# Microsecond_clock_LEDs.net
KiCad netlist of a schematic drawn in EAGLE
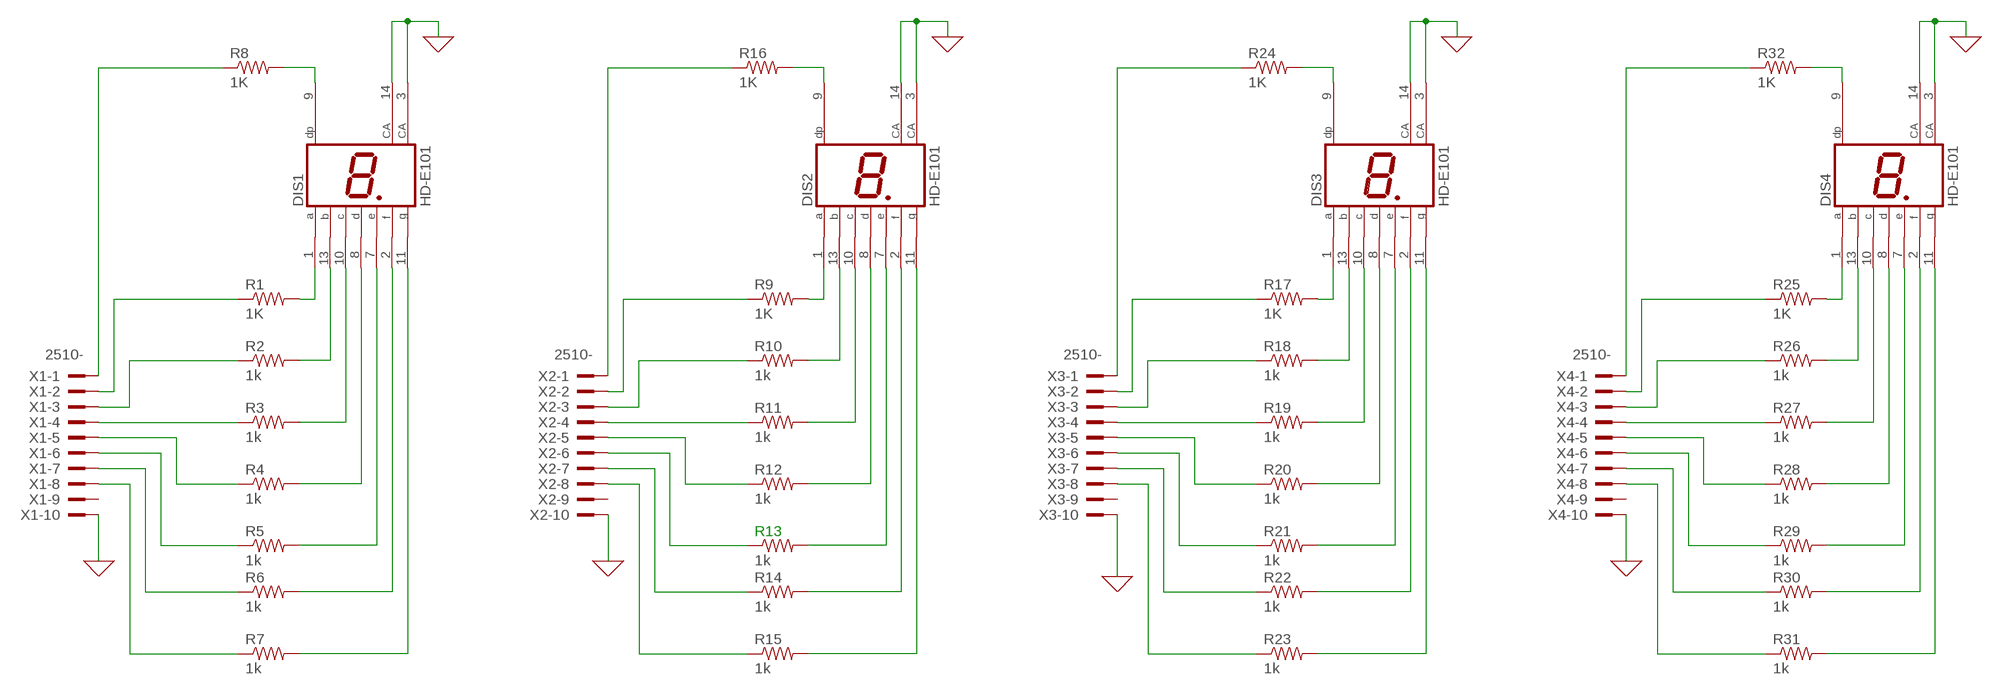
[diagram p0: schematic, sheet 1]

(export (version "E")
  (design (tool "Eeschema 10.0.6"))
  (components
    (comp (ref "DIS1")
      (value "HD-E101")
      (footprint "eagle-import:HDSP-I")
      (libsource (lib "eagle-import") (part "HD-E101"))
    )
    (comp (ref "DIS2")
      (value "HD-E101")
      (footprint "eagle-import:HDSP-I")
      (libsource (lib "eagle-import") (part "HD-E101"))
    )
    (comp (ref "DIS3")
      (value "HD-E101")
      (footprint "eagle-import:HDSP-I")
      (libsource (lib "eagle-import") (part "HD-E101"))
    )
    (comp (ref "DIS4")
      (value "HD-E101")
      (footprint "eagle-import:HDSP-I")
      (libsource (lib "eagle-import") (part "HD-E101"))
    )
    (comp (ref "R1")
      (value "1K")
      (footprint "eagle-import:0207_7")
      (libsource (lib "eagle-import") (part "R-US_0207/7"))
    )
    (comp (ref "R2")
      (value "1k")
      (footprint "eagle-import:0207_7")
      (libsource (lib "eagle-import") (part "R-US_0207/7"))
    )
    (comp (ref "R3")
      (value "1k")
      (footprint "eagle-import:0207_7")
      (libsource (lib "eagle-import") (part "R-US_0207/7"))
    )
    (comp (ref "R4")
      (value "1k")
      (footprint "eagle-import:0207_7")
      (libsource (lib "eagle-import") (part "R-US_0207/7"))
    )
    (comp (ref "R5")
      (value "1k")
      (footprint "eagle-import:0207_7")
      (libsource (lib "eagle-import") (part "R-US_0207/7"))
    )
    (comp (ref "R6")
      (value "1k")
      (footprint "eagle-import:0207_7")
      (libsource (lib "eagle-import") (part "R-US_0207/7"))
    )
    (comp (ref "R7")
      (value "1k")
      (footprint "eagle-import:0207_7")
      (libsource (lib "eagle-import") (part "R-US_0207/7"))
    )
    (comp (ref "R8")
      (value "1K")
      (footprint "eagle-import:0207_7")
      (libsource (lib "eagle-import") (part "R-US_0207/7"))
    )
    (comp (ref "R9")
      (value "1K")
      (footprint "eagle-import:0207_7")
      (libsource (lib "eagle-import") (part "R-US_0207/7"))
    )
    (comp (ref "R10")
      (value "1k")
      (footprint "eagle-import:0207_7")
      (libsource (lib "eagle-import") (part "R-US_0207/7"))
    )
    (comp (ref "R11")
      (value "1k")
      (footprint "eagle-import:0207_7")
      (libsource (lib "eagle-import") (part "R-US_0207/7"))
    )
    (comp (ref "R12")
      (value "1k")
      (footprint "eagle-import:0207_7")
      (libsource (lib "eagle-import") (part "R-US_0207/7"))
    )
    (comp (ref "R13")
      (value "1k")
      (footprint "eagle-import:0207_7")
      (libsource (lib "eagle-import") (part "R-US_0207/7"))
    )
    (comp (ref "R14")
      (value "1k")
      (footprint "eagle-import:0207_7")
      (libsource (lib "eagle-import") (part "R-US_0207/7"))
    )
    (comp (ref "R15")
      (value "1k")
      (footprint "eagle-import:0207_7")
      (libsource (lib "eagle-import") (part "R-US_0207/7"))
    )
    (comp (ref "R16")
      (value "1K")
      (footprint "eagle-import:0207_7")
      (libsource (lib "eagle-import") (part "R-US_0207/7"))
    )
    (comp (ref "R17")
      (value "1K")
      (footprint "eagle-import:0207_7")
      (libsource (lib "eagle-import") (part "R-US_0207/7"))
    )
    (comp (ref "R18")
      (value "1k")
      (footprint "eagle-import:0207_7")
      (libsource (lib "eagle-import") (part "R-US_0207/7"))
    )
    (comp (ref "R19")
      (value "1k")
      (footprint "eagle-import:0207_7")
      (libsource (lib "eagle-import") (part "R-US_0207/7"))
    )
    (comp (ref "R20")
      (value "1k")
      (footprint "eagle-import:0207_7")
      (libsource (lib "eagle-import") (part "R-US_0207/7"))
    )
    (comp (ref "R21")
      (value "1k")
      (footprint "eagle-import:0207_7")
      (libsource (lib "eagle-import") (part "R-US_0207/7"))
    )
    (comp (ref "R22")
      (value "1k")
      (footprint "eagle-import:0207_7")
      (libsource (lib "eagle-import") (part "R-US_0207/7"))
    )
    (comp (ref "R23")
      (value "1k")
      (footprint "eagle-import:0207_7")
      (libsource (lib "eagle-import") (part "R-US_0207/7"))
    )
    (comp (ref "R24")
      (value "1K")
      (footprint "eagle-import:0207_7")
      (libsource (lib "eagle-import") (part "R-US_0207/7"))
    )
    (comp (ref "R25")
      (value "1K")
      (footprint "eagle-import:0207_7")
      (libsource (lib "eagle-import") (part "R-US_0207/7"))
    )
    (comp (ref "R26")
      (value "1k")
      (footprint "eagle-import:0207_7")
      (libsource (lib "eagle-import") (part "R-US_0207/7"))
    )
    (comp (ref "R27")
      (value "1k")
      (footprint "eagle-import:0207_7")
      (libsource (lib "eagle-import") (part "R-US_0207/7"))
    )
    (comp (ref "R28")
      (value "1k")
      (footprint "eagle-import:0207_7")
      (libsource (lib "eagle-import") (part "R-US_0207/7"))
    )
    (comp (ref "R29")
      (value "1k")
      (footprint "eagle-import:0207_7")
      (libsource (lib "eagle-import") (part "R-US_0207/7"))
    )
    (comp (ref "R30")
      (value "1k")
      (footprint "eagle-import:0207_7")
      (libsource (lib "eagle-import") (part "R-US_0207/7"))
    )
    (comp (ref "R31")
      (value "1k")
      (footprint "eagle-import:0207_7")
      (libsource (lib "eagle-import") (part "R-US_0207/7"))
    )
    (comp (ref "R32")
      (value "1K")
      (footprint "eagle-import:0207_7")
      (libsource (lib "eagle-import") (part "R-US_0207/7"))
    )
    (comp (ref "X1")
      (value "2510-")
      (footprint "eagle-import:PAK100_2500-10")
      (fields (field (name "MF") "3M") (field (name "MPN") "2510-6002UB"))
      (libsource (lib "eagle-import") (part "2510-"))
    )
    (comp (ref "X2")
      (value "2510-")
      (footprint "eagle-import:PAK100_2500-10")
      (fields (field (name "MF") "3M") (field (name "MPN") "2510-6002UB"))
      (libsource (lib "eagle-import") (part "2510-"))
    )
    (comp (ref "X3")
      (value "2510-")
      (footprint "eagle-import:PAK100_2500-10")
      (fields (field (name "MF") "3M") (field (name "MPN") "2510-6002UB"))
      (libsource (lib "eagle-import") (part "2510-"))
    )
    (comp (ref "X4")
      (value "2510-")
      (footprint "eagle-import:PAK100_2500-10")
      (fields (field (name "MF") "3M") (field (name "MPN") "2510-6002UB"))
      (libsource (lib "eagle-import") (part "2510-"))
    )
  )
  (nets
    (net (code "1") (name "GND") (class "Default")
      (node (ref "DIS1") (pin "14") (pinfunction "CA_14") (pintype "passive"))
      (node (ref "DIS1") (pin "3") (pinfunction "CA_3") (pintype "passive"))
      (node (ref "DIS2") (pin "14") (pinfunction "CA_14") (pintype "passive"))
      (node (ref "DIS2") (pin "3") (pinfunction "CA_3") (pintype "passive"))
      (node (ref "DIS3") (pin "14") (pinfunction "CA_14") (pintype "passive"))
      (node (ref "DIS3") (pin "3") (pinfunction "CA_3") (pintype "passive"))
      (node (ref "DIS4") (pin "14") (pinfunction "CA_14") (pintype "passive"))
      (node (ref "DIS4") (pin "3") (pinfunction "CA_3") (pintype "passive"))
      (node (ref "X1") (pin "10") (pinfunction "KL_10") (pintype "passive"))
      (node (ref "X2") (pin "10") (pinfunction "KL_10") (pintype "passive"))
      (node (ref "X3") (pin "10") (pinfunction "KL_10") (pintype "passive"))
      (node (ref "X4") (pin "10") (pinfunction "KL_10") (pintype "passive"))
    )
    (net (code "2") (name "Net-(DIS1-A)") (class "Default")
      (node (ref "DIS1") (pin "1") (pinfunction "A_1") (pintype "passive"))
      (node (ref "R1") (pin "2") (pinfunction "2_2") (pintype "passive"))
    )
    (net (code "3") (name "Net-(DIS1-B)") (class "Default")
      (node (ref "DIS1") (pin "13") (pinfunction "B_13") (pintype "passive"))
      (node (ref "R2") (pin "2") (pinfunction "2_2") (pintype "passive"))
    )
    (net (code "4") (name "Net-(DIS1-C)") (class "Default")
      (node (ref "DIS1") (pin "10") (pinfunction "C_10") (pintype "passive"))
      (node (ref "R3") (pin "2") (pinfunction "2_2") (pintype "passive"))
    )
    (net (code "5") (name "Net-(DIS1-D)") (class "Default")
      (node (ref "DIS1") (pin "8") (pinfunction "D_8") (pintype "passive"))
      (node (ref "R4") (pin "2") (pinfunction "2_2") (pintype "passive"))
    )
    (net (code "6") (name "Net-(DIS1-DP)") (class "Default")
      (node (ref "DIS1") (pin "9") (pinfunction "DP_9") (pintype "passive"))
      (node (ref "R8") (pin "2") (pinfunction "2_2") (pintype "passive"))
    )
    (net (code "7") (name "Net-(DIS1-E)") (class "Default")
      (node (ref "DIS1") (pin "7") (pinfunction "E_7") (pintype "passive"))
      (node (ref "R5") (pin "2") (pinfunction "2_2") (pintype "passive"))
    )
    (net (code "8") (name "Net-(DIS1-F)") (class "Default")
      (node (ref "DIS1") (pin "2") (pinfunction "F_2") (pintype "passive"))
      (node (ref "R6") (pin "2") (pinfunction "2_2") (pintype "passive"))
    )
    (net (code "9") (name "Net-(DIS1-G)") (class "Default")
      (node (ref "DIS1") (pin "11") (pinfunction "G_11") (pintype "passive"))
      (node (ref "R7") (pin "2") (pinfunction "2_2") (pintype "passive"))
    )
    (net (code "10") (name "Net-(DIS2-A)") (class "Default")
      (node (ref "DIS2") (pin "1") (pinfunction "A_1") (pintype "passive"))
      (node (ref "R9") (pin "2") (pinfunction "2_2") (pintype "passive"))
    )
    (net (code "11") (name "Net-(DIS2-B)") (class "Default")
      (node (ref "DIS2") (pin "13") (pinfunction "B_13") (pintype "passive"))
      (node (ref "R10") (pin "2") (pinfunction "2_2") (pintype "passive"))
    )
    (net (code "12") (name "Net-(DIS2-C)") (class "Default")
      (node (ref "DIS2") (pin "10") (pinfunction "C_10") (pintype "passive"))
      (node (ref "R11") (pin "2") (pinfunction "2_2") (pintype "passive"))
    )
    (net (code "13") (name "Net-(DIS2-D)") (class "Default")
      (node (ref "DIS2") (pin "8") (pinfunction "D_8") (pintype "passive"))
      (node (ref "R12") (pin "2") (pinfunction "2_2") (pintype "passive"))
    )
    (net (code "14") (name "Net-(DIS2-DP)") (class "Default")
      (node (ref "DIS2") (pin "9") (pinfunction "DP_9") (pintype "passive"))
      (node (ref "R16") (pin "2") (pinfunction "2_2") (pintype "passive"))
    )
    (net (code "15") (name "Net-(DIS2-E)") (class "Default")
      (node (ref "DIS2") (pin "7") (pinfunction "E_7") (pintype "passive"))
      (node (ref "R13") (pin "2") (pinfunction "2_2") (pintype "passive"))
    )
    (net (code "16") (name "Net-(DIS2-F)") (class "Default")
      (node (ref "DIS2") (pin "2") (pinfunction "F_2") (pintype "passive"))
      (node (ref "R14") (pin "2") (pinfunction "2_2") (pintype "passive"))
    )
    (net (code "17") (name "Net-(DIS2-G)") (class "Default")
      (node (ref "DIS2") (pin "11") (pinfunction "G_11") (pintype "passive"))
      (node (ref "R15") (pin "2") (pinfunction "2_2") (pintype "passive"))
    )
    (net (code "18") (name "Net-(DIS3-A)") (class "Default")
      (node (ref "DIS3") (pin "1") (pinfunction "A_1") (pintype "passive"))
      (node (ref "R17") (pin "2") (pinfunction "2_2") (pintype "passive"))
    )
    (net (code "19") (name "Net-(DIS3-B)") (class "Default")
      (node (ref "DIS3") (pin "13") (pinfunction "B_13") (pintype "passive"))
      (node (ref "R18") (pin "2") (pinfunction "2_2") (pintype "passive"))
    )
    (net (code "20") (name "Net-(DIS3-C)") (class "Default")
      (node (ref "DIS3") (pin "10") (pinfunction "C_10") (pintype "passive"))
      (node (ref "R19") (pin "2") (pinfunction "2_2") (pintype "passive"))
    )
    (net (code "21") (name "Net-(DIS3-D)") (class "Default")
      (node (ref "DIS3") (pin "8") (pinfunction "D_8") (pintype "passive"))
      (node (ref "R20") (pin "2") (pinfunction "2_2") (pintype "passive"))
    )
    (net (code "22") (name "Net-(DIS3-DP)") (class "Default")
      (node (ref "DIS3") (pin "9") (pinfunction "DP_9") (pintype "passive"))
      (node (ref "R24") (pin "2") (pinfunction "2_2") (pintype "passive"))
    )
    (net (code "23") (name "Net-(DIS3-E)") (class "Default")
      (node (ref "DIS3") (pin "7") (pinfunction "E_7") (pintype "passive"))
      (node (ref "R21") (pin "2") (pinfunction "2_2") (pintype "passive"))
    )
    (net (code "24") (name "Net-(DIS3-F)") (class "Default")
      (node (ref "DIS3") (pin "2") (pinfunction "F_2") (pintype "passive"))
      (node (ref "R22") (pin "2") (pinfunction "2_2") (pintype "passive"))
    )
    (net (code "25") (name "Net-(DIS3-G)") (class "Default")
      (node (ref "DIS3") (pin "11") (pinfunction "G_11") (pintype "passive"))
      (node (ref "R23") (pin "2") (pinfunction "2_2") (pintype "passive"))
    )
    (net (code "26") (name "Net-(DIS4-A)") (class "Default")
      (node (ref "DIS4") (pin "1") (pinfunction "A_1") (pintype "passive"))
      (node (ref "R25") (pin "2") (pinfunction "2_2") (pintype "passive"))
    )
    (net (code "27") (name "Net-(DIS4-B)") (class "Default")
      (node (ref "DIS4") (pin "13") (pinfunction "B_13") (pintype "passive"))
      (node (ref "R26") (pin "2") (pinfunction "2_2") (pintype "passive"))
    )
    (net (code "28") (name "Net-(DIS4-C)") (class "Default")
      (node (ref "DIS4") (pin "10") (pinfunction "C_10") (pintype "passive"))
      (node (ref "R27") (pin "2") (pinfunction "2_2") (pintype "passive"))
    )
    (net (code "29") (name "Net-(DIS4-D)") (class "Default")
      (node (ref "DIS4") (pin "8") (pinfunction "D_8") (pintype "passive"))
      (node (ref "R28") (pin "2") (pinfunction "2_2") (pintype "passive"))
    )
    (net (code "30") (name "Net-(DIS4-DP)") (class "Default")
      (node (ref "DIS4") (pin "9") (pinfunction "DP_9") (pintype "passive"))
      (node (ref "R32") (pin "2") (pinfunction "2_2") (pintype "passive"))
    )
    (net (code "31") (name "Net-(DIS4-E)") (class "Default")
      (node (ref "DIS4") (pin "7") (pinfunction "E_7") (pintype "passive"))
      (node (ref "R29") (pin "2") (pinfunction "2_2") (pintype "passive"))
    )
    (net (code "32") (name "Net-(DIS4-F)") (class "Default")
      (node (ref "DIS4") (pin "2") (pinfunction "F_2") (pintype "passive"))
      (node (ref "R30") (pin "2") (pinfunction "2_2") (pintype "passive"))
    )
    (net (code "33") (name "Net-(DIS4-G)") (class "Default")
      (node (ref "DIS4") (pin "11") (pinfunction "G_11") (pintype "passive"))
      (node (ref "R31") (pin "2") (pinfunction "2_2") (pintype "passive"))
    )
    (net (code "34") (name "Net-(X1A-KL)") (class "Default")
      (node (ref "R8") (pin "1") (pinfunction "1_1") (pintype "passive"))
      (node (ref "X1") (pin "1") (pinfunction "KL_1") (pintype "passive"))
    )
    (net (code "35") (name "Net-(X1C-KL)") (class "Default")
      (node (ref "R1") (pin "1") (pinfunction "1_1") (pintype "passive"))
      (node (ref "X1") (pin "2") (pinfunction "KL_2") (pintype "passive"))
    )
    (net (code "36") (name "Net-(X1D-KL)") (class "Default")
      (node (ref "R2") (pin "1") (pinfunction "1_1") (pintype "passive"))
      (node (ref "X1") (pin "3") (pinfunction "KL_3") (pintype "passive"))
    )
    (net (code "37") (name "Net-(X1E-KL)") (class "Default")
      (node (ref "R3") (pin "1") (pinfunction "1_1") (pintype "passive"))
      (node (ref "X1") (pin "4") (pinfunction "KL_4") (pintype "passive"))
    )
    (net (code "38") (name "Net-(X1F-KL)") (class "Default")
      (node (ref "R4") (pin "1") (pinfunction "1_1") (pintype "passive"))
      (node (ref "X1") (pin "5") (pinfunction "KL_5") (pintype "passive"))
    )
    (net (code "39") (name "Net-(X1G-KL)") (class "Default")
      (node (ref "R5") (pin "1") (pinfunction "1_1") (pintype "passive"))
      (node (ref "X1") (pin "6") (pinfunction "KL_6") (pintype "passive"))
    )
    (net (code "40") (name "Net-(X1H-KL)") (class "Default")
      (node (ref "R6") (pin "1") (pinfunction "1_1") (pintype "passive"))
      (node (ref "X1") (pin "7") (pinfunction "KL_7") (pintype "passive"))
    )
    (net (code "41") (name "Net-(X1I-KL)") (class "Default")
      (node (ref "R7") (pin "1") (pinfunction "1_1") (pintype "passive"))
      (node (ref "X1") (pin "8") (pinfunction "KL_8") (pintype "passive"))
    )
    (net (code "42") (name "Net-(X2A-KL)") (class "Default")
      (node (ref "R16") (pin "1") (pinfunction "1_1") (pintype "passive"))
      (node (ref "X2") (pin "1") (pinfunction "KL_1") (pintype "passive"))
    )
    (net (code "43") (name "Net-(X2C-KL)") (class "Default")
      (node (ref "R9") (pin "1") (pinfunction "1_1") (pintype "passive"))
      (node (ref "X2") (pin "2") (pinfunction "KL_2") (pintype "passive"))
    )
    (net (code "44") (name "Net-(X2D-KL)") (class "Default")
      (node (ref "R10") (pin "1") (pinfunction "1_1") (pintype "passive"))
      (node (ref "X2") (pin "3") (pinfunction "KL_3") (pintype "passive"))
    )
    (net (code "45") (name "Net-(X2E-KL)") (class "Default")
      (node (ref "R11") (pin "1") (pinfunction "1_1") (pintype "passive"))
      (node (ref "X2") (pin "4") (pinfunction "KL_4") (pintype "passive"))
    )
    (net (code "46") (name "Net-(X2F-KL)") (class "Default")
      (node (ref "R12") (pin "1") (pinfunction "1_1") (pintype "passive"))
      (node (ref "X2") (pin "5") (pinfunction "KL_5") (pintype "passive"))
    )
    (net (code "47") (name "Net-(X2G-KL)") (class "Default")
      (node (ref "R13") (pin "1") (pinfunction "1_1") (pintype "passive"))
      (node (ref "X2") (pin "6") (pinfunction "KL_6") (pintype "passive"))
    )
    (net (code "48") (name "Net-(X2H-KL)") (class "Default")
      (node (ref "R14") (pin "1") (pinfunction "1_1") (pintype "passive"))
      (node (ref "X2") (pin "7") (pinfunction "KL_7") (pintype "passive"))
    )
    (net (code "49") (name "Net-(X2I-KL)") (class "Default")
      (node (ref "R15") (pin "1") (pinfunction "1_1") (pintype "passive"))
      (node (ref "X2") (pin "8") (pinfunction "KL_8") (pintype "passive"))
    )
    (net (code "50") (name "Net-(X3A-KL)") (class "Default")
      (node (ref "R24") (pin "1") (pinfunction "1_1") (pintype "passive"))
      (node (ref "X3") (pin "1") (pinfunction "KL_1") (pintype "passive"))
    )
    (net (code "51") (name "Net-(X3C-KL)") (class "Default")
      (node (ref "R17") (pin "1") (pinfunction "1_1") (pintype "passive"))
      (node (ref "X3") (pin "2") (pinfunction "KL_2") (pintype "passive"))
    )
    (net (code "52") (name "Net-(X3D-KL)") (class "Default")
      (node (ref "R18") (pin "1") (pinfunction "1_1") (pintype "passive"))
      (node (ref "X3") (pin "3") (pinfunction "KL_3") (pintype "passive"))
    )
    (net (code "53") (name "Net-(X3E-KL)") (class "Default")
      (node (ref "R19") (pin "1") (pinfunction "1_1") (pintype "passive"))
      (node (ref "X3") (pin "4") (pinfunction "KL_4") (pintype "passive"))
    )
    (net (code "54") (name "Net-(X3F-KL)") (class "Default")
      (node (ref "R20") (pin "1") (pinfunction "1_1") (pintype "passive"))
      (node (ref "X3") (pin "5") (pinfunction "KL_5") (pintype "passive"))
    )
    (net (code "55") (name "Net-(X3G-KL)") (class "Default")
      (node (ref "R21") (pin "1") (pinfunction "1_1") (pintype "passive"))
      (node (ref "X3") (pin "6") (pinfunction "KL_6") (pintype "passive"))
    )
    (net (code "56") (name "Net-(X3H-KL)") (class "Default")
      (node (ref "R22") (pin "1") (pinfunction "1_1") (pintype "passive"))
      (node (ref "X3") (pin "7") (pinfunction "KL_7") (pintype "passive"))
    )
    (net (code "57") (name "Net-(X3I-KL)") (class "Default")
      (node (ref "R23") (pin "1") (pinfunction "1_1") (pintype "passive"))
      (node (ref "X3") (pin "8") (pinfunction "KL_8") (pintype "passive"))
    )
    (net (code "58") (name "Net-(X4A-KL)") (class "Default")
      (node (ref "R32") (pin "1") (pinfunction "1_1") (pintype "passive"))
      (node (ref "X4") (pin "1") (pinfunction "KL_1") (pintype "passive"))
    )
    (net (code "59") (name "Net-(X4C-KL)") (class "Default")
      (node (ref "R25") (pin "1") (pinfunction "1_1") (pintype "passive"))
      (node (ref "X4") (pin "2") (pinfunction "KL_2") (pintype "passive"))
    )
    (net (code "60") (name "Net-(X4D-KL)") (class "Default")
      (node (ref "R26") (pin "1") (pinfunction "1_1") (pintype "passive"))
      (node (ref "X4") (pin "3") (pinfunction "KL_3") (pintype "passive"))
    )
    (net (code "61") (name "Net-(X4E-KL)") (class "Default")
      (node (ref "R27") (pin "1") (pinfunction "1_1") (pintype "passive"))
      (node (ref "X4") (pin "4") (pinfunction "KL_4") (pintype "passive"))
    )
    (net (code "62") (name "Net-(X4F-KL)") (class "Default")
      (node (ref "R28") (pin "1") (pinfunction "1_1") (pintype "passive"))
      (node (ref "X4") (pin "5") (pinfunction "KL_5") (pintype "passive"))
    )
    (net (code "63") (name "Net-(X4G-KL)") (class "Default")
      (node (ref "R29") (pin "1") (pinfunction "1_1") (pintype "passive"))
      (node (ref "X4") (pin "6") (pinfunction "KL_6") (pintype "passive"))
    )
    (net (code "64") (name "Net-(X4H-KL)") (class "Default")
      (node (ref "R30") (pin "1") (pinfunction "1_1") (pintype "passive"))
      (node (ref "X4") (pin "7") (pinfunction "KL_7") (pintype "passive"))
    )
    (net (code "65") (name "Net-(X4I-KL)") (class "Default")
      (node (ref "R31") (pin "1") (pinfunction "1_1") (pintype "passive"))
      (node (ref "X4") (pin "8") (pinfunction "KL_8") (pintype "passive"))
    )
    (net (code "66") (name "unconnected-(X1J-KL-Pad9)") (class "Default")
      (node (ref "X1") (pin "9") (pinfunction "KL_9") (pintype "passive"))
    )
    (net (code "67") (name "unconnected-(X2J-KL-Pad9)") (class "Default")
      (node (ref "X2") (pin "9") (pinfunction "KL_9") (pintype "passive"))
    )
    (net (code "68") (name "unconnected-(X3J-KL-Pad9)") (class "Default")
      (node (ref "X3") (pin "9") (pinfunction "KL_9") (pintype "passive"))
    )
    (net (code "69") (name "unconnected-(X4J-KL-Pad9)") (class "Default")
      (node (ref "X4") (pin "9") (pinfunction "KL_9") (pintype "passive"))
    )
  )
)
